# projet_pcb_bluepill_f103_SchDoc.net
KiCad netlist of a schematic drawn in EasyEDA
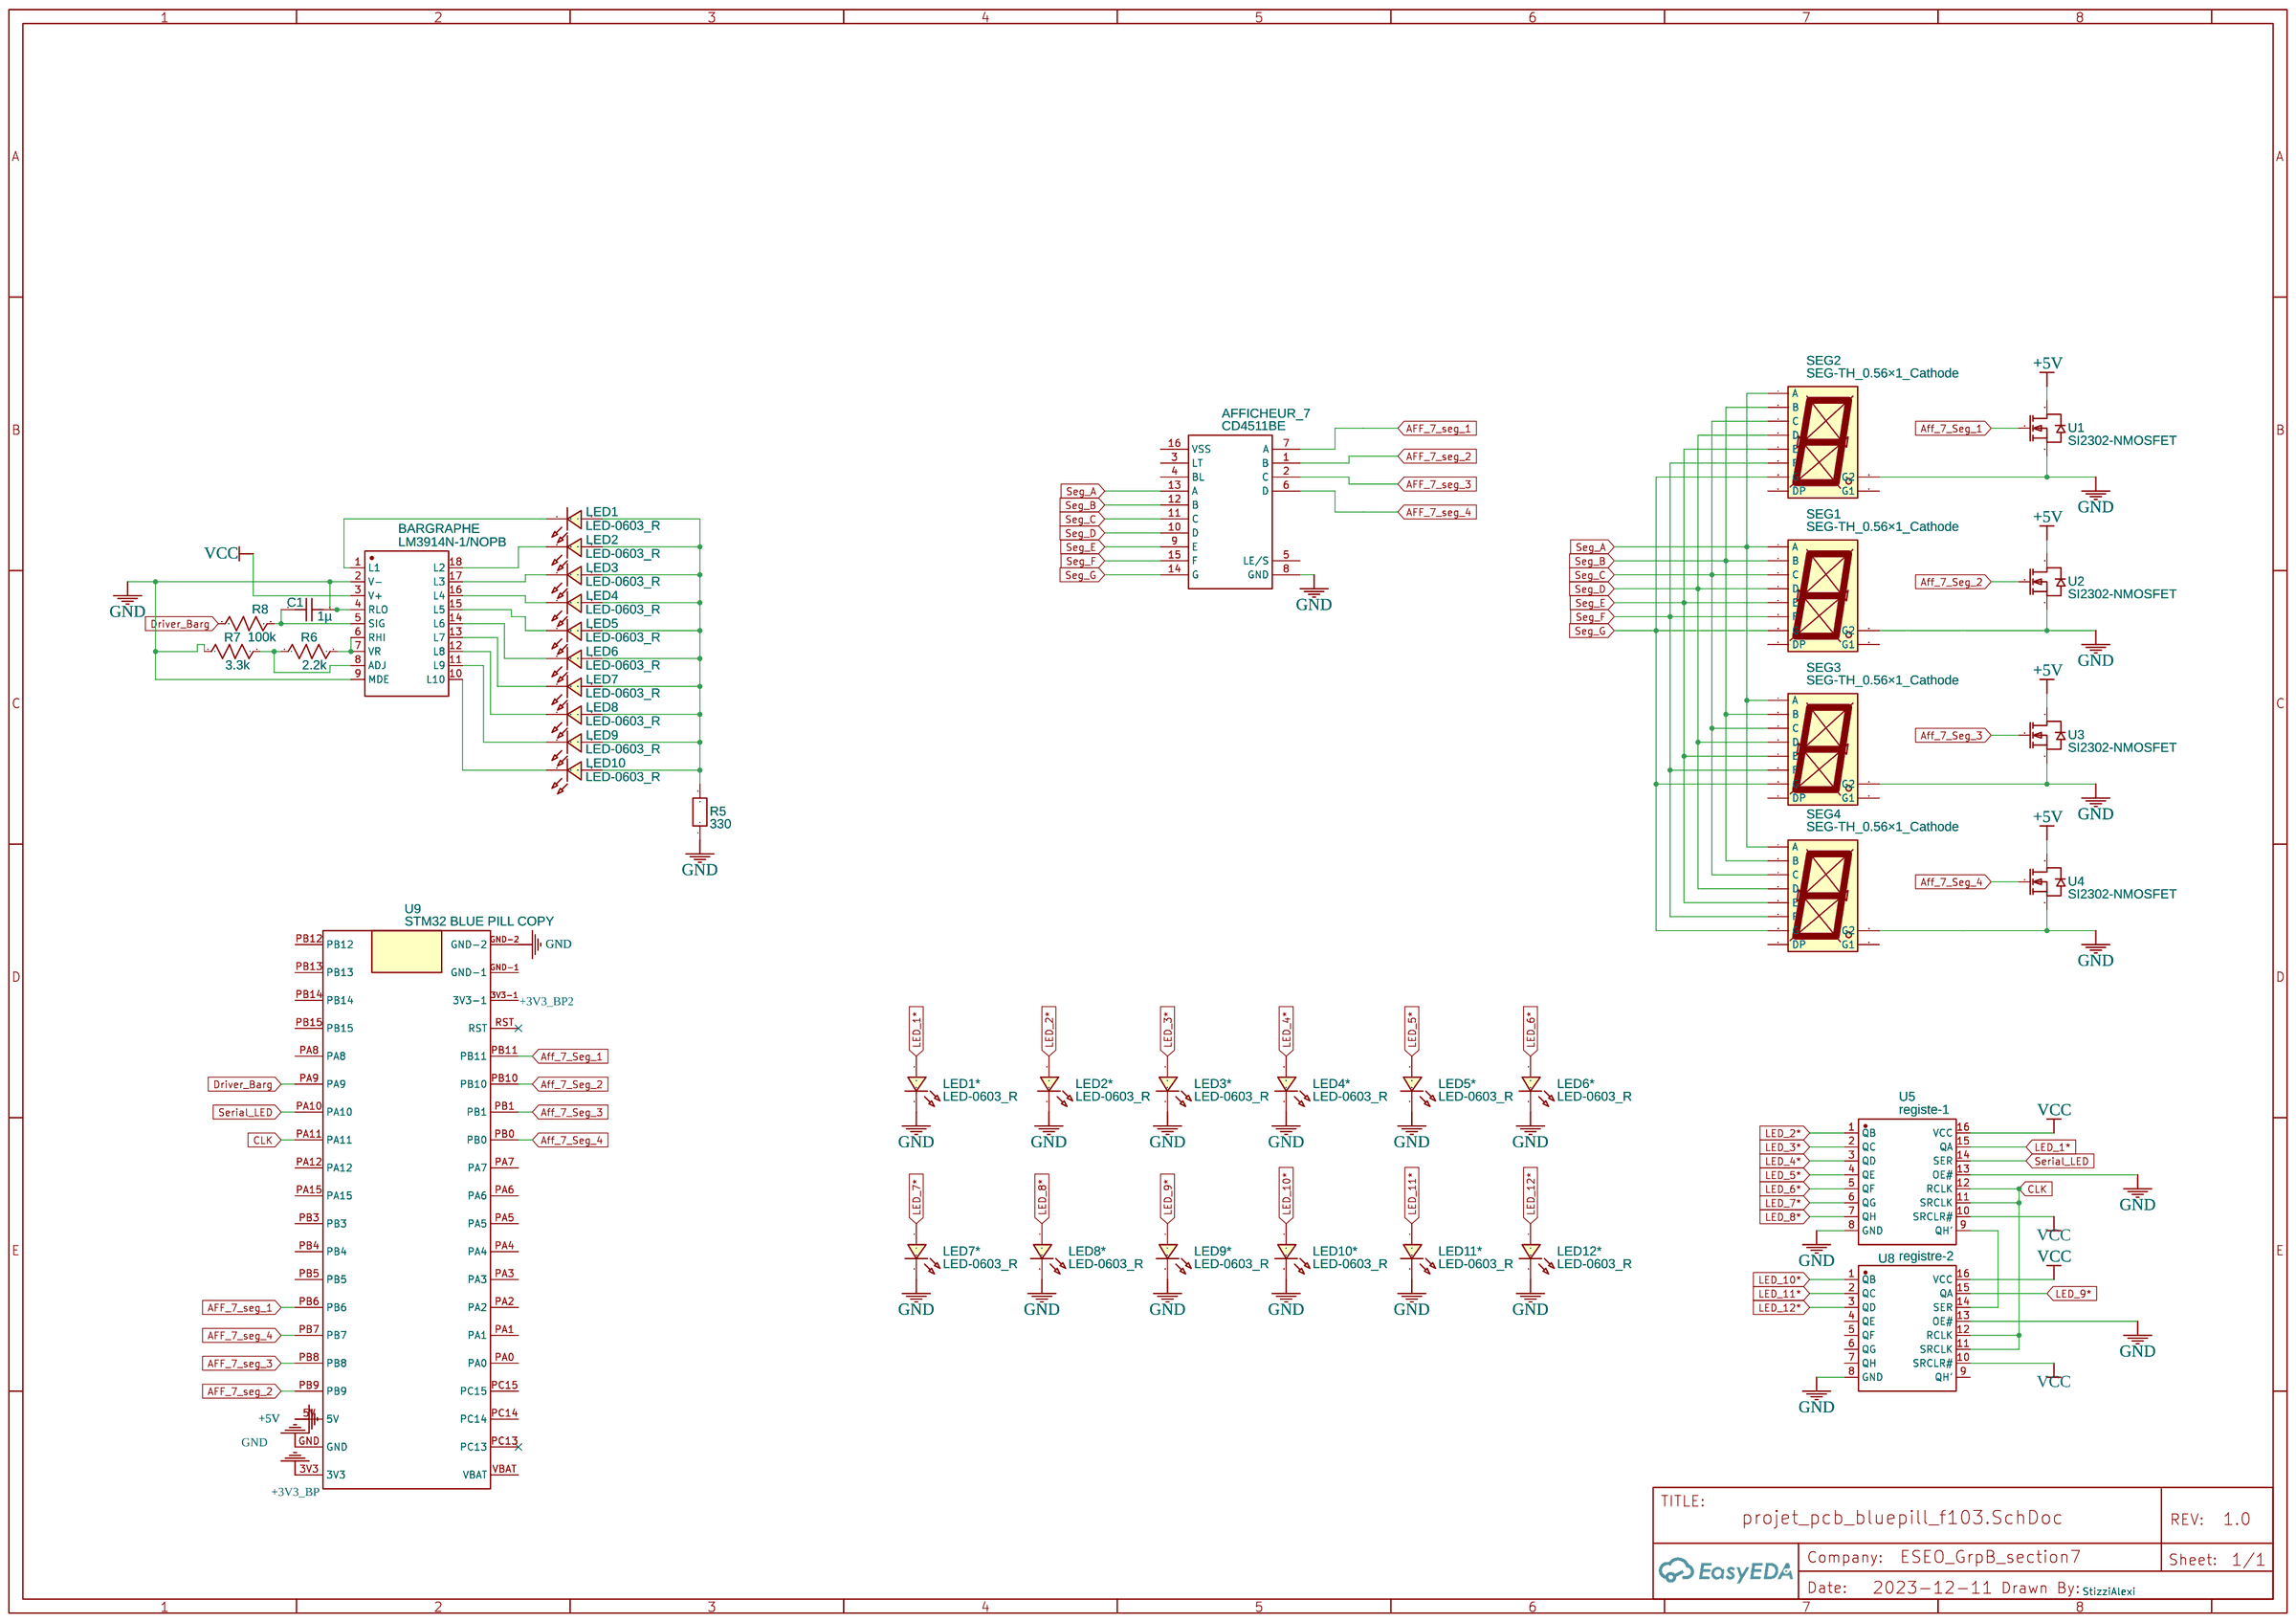
[diagram p0: schematic sheet]

(export (version "E")
  (design (tool "Eeschema 10.0.6"))
  (components
    (comp (ref "AFFICHEUR_7") (value "CD4511BE") (libsource (lib "") (part "CD4511BE")))
    (comp (ref "BARGRAPHE")
      (value "LM3914N-1/NOPB")
      (fields (field (name "Manufacturer") "TI(德州仪器)"))
      (libsource (lib "") (part "LM3914N-1/NOPB"))
    )
    (comp (ref "C1") (value "1µ") (libsource (lib "") (part "C_0603_US")))
    (comp (ref "LED1")
      (value "LED-0603_R")
      (fields
        (field (name "Manufacturer Part") "19-217/R6C-AL1M2VY/3T")
        (field (name "Manufacturer") "EVERLIGHT(台湾亿光)")
      )
      (libsource (lib "") (part "LED-0603_R_1"))
    )
    (comp (ref "LED1*")
      (value "LED-0603_R")
      (fields
        (field (name "Manufacturer Part") "19-217/R6C-AL1M2VY/3T")
        (field (name "Manufacturer") "EVERLIGHT(台湾亿光)")
      )
      (libsource (lib "") (part "LED-0603_R"))
    )
    (comp (ref "LED2")
      (value "LED-0603_R")
      (fields
        (field (name "Manufacturer Part") "19-217/R6C-AL1M2VY/3T")
        (field (name "Manufacturer") "EVERLIGHT(台湾亿光)")
      )
      (libsource (lib "") (part "LED-0603_R_1"))
    )
    (comp (ref "LED2*")
      (value "LED-0603_R")
      (fields
        (field (name "Manufacturer Part") "19-217/R6C-AL1M2VY/3T")
        (field (name "Manufacturer") "EVERLIGHT(台湾亿光)")
      )
      (libsource (lib "") (part "LED-0603_R_8"))
    )
    (comp (ref "LED3")
      (value "LED-0603_R")
      (fields
        (field (name "Manufacturer Part") "19-217/R6C-AL1M2VY/3T")
        (field (name "Manufacturer") "EVERLIGHT(台湾亿光)")
      )
      (libsource (lib "") (part "LED-0603_R_1"))
    )
    (comp (ref "LED3*")
      (value "LED-0603_R")
      (fields
        (field (name "Manufacturer Part") "19-217/R6C-AL1M2VY/3T")
        (field (name "Manufacturer") "EVERLIGHT(台湾亿光)")
      )
      (libsource (lib "") (part "LED-0603_R_2"))
    )
    (comp (ref "LED4")
      (value "LED-0603_R")
      (fields
        (field (name "Manufacturer Part") "19-217/R6C-AL1M2VY/3T")
        (field (name "Manufacturer") "EVERLIGHT(台湾亿光)")
      )
      (libsource (lib "") (part "LED-0603_R_1"))
    )
    (comp (ref "LED4*")
      (value "LED-0603_R")
      (fields
        (field (name "Manufacturer Part") "19-217/R6C-AL1M2VY/3T")
        (field (name "Manufacturer") "EVERLIGHT(台湾亿光)")
      )
      (libsource (lib "") (part "LED-0603_R_6"))
    )
    (comp (ref "LED5")
      (value "LED-0603_R")
      (fields
        (field (name "Manufacturer Part") "19-217/R6C-AL1M2VY/3T")
        (field (name "Manufacturer") "EVERLIGHT(台湾亿光)")
      )
      (libsource (lib "") (part "LED-0603_R_1"))
    )
    (comp (ref "LED5*")
      (value "LED-0603_R")
      (fields
        (field (name "Manufacturer Part") "19-217/R6C-AL1M2VY/3T")
        (field (name "Manufacturer") "EVERLIGHT(台湾亿光)")
      )
      (libsource (lib "") (part "LED-0603_R_7"))
    )
    (comp (ref "LED6")
      (value "LED-0603_R")
      (fields
        (field (name "Manufacturer Part") "19-217/R6C-AL1M2VY/3T")
        (field (name "Manufacturer") "EVERLIGHT(台湾亿光)")
      )
      (libsource (lib "") (part "LED-0603_R_1"))
    )
    (comp (ref "LED6*")
      (value "LED-0603_R")
      (fields
        (field (name "Manufacturer Part") "19-217/R6C-AL1M2VY/3T")
        (field (name "Manufacturer") "EVERLIGHT(台湾亿光)")
      )
      (libsource (lib "") (part "LED-0603_R_12"))
    )
    (comp (ref "LED7")
      (value "LED-0603_R")
      (fields
        (field (name "Manufacturer Part") "19-217/R6C-AL1M2VY/3T")
        (field (name "Manufacturer") "EVERLIGHT(台湾亿光)")
      )
      (libsource (lib "") (part "LED-0603_R_1"))
    )
    (comp (ref "LED7*")
      (value "LED-0603_R")
      (fields
        (field (name "Manufacturer Part") "19-217/R6C-AL1M2VY/3T")
        (field (name "Manufacturer") "EVERLIGHT(台湾亿光)")
      )
      (libsource (lib "") (part "LED-0603_R_4"))
    )
    (comp (ref "LED8")
      (value "LED-0603_R")
      (fields
        (field (name "Manufacturer Part") "19-217/R6C-AL1M2VY/3T")
        (field (name "Manufacturer") "EVERLIGHT(台湾亿光)")
      )
      (libsource (lib "") (part "LED-0603_R_1"))
    )
    (comp (ref "LED8*")
      (value "LED-0603_R")
      (fields
        (field (name "Manufacturer Part") "19-217/R6C-AL1M2VY/3T")
        (field (name "Manufacturer") "EVERLIGHT(台湾亿光)")
      )
      (libsource (lib "") (part "LED-0603_R_5"))
    )
    (comp (ref "LED9")
      (value "LED-0603_R")
      (fields
        (field (name "Manufacturer Part") "19-217/R6C-AL1M2VY/3T")
        (field (name "Manufacturer") "EVERLIGHT(台湾亿光)")
      )
      (libsource (lib "") (part "LED-0603_R_1"))
    )
    (comp (ref "LED9*")
      (value "LED-0603_R")
      (fields
        (field (name "Manufacturer Part") "19-217/R6C-AL1M2VY/3T")
        (field (name "Manufacturer") "EVERLIGHT(台湾亿光)")
      )
      (libsource (lib "") (part "LED-0603_R_9"))
    )
    (comp (ref "LED10")
      (value "LED-0603_R")
      (fields
        (field (name "Manufacturer Part") "19-217/R6C-AL1M2VY/3T")
        (field (name "Manufacturer") "EVERLIGHT(台湾亿光)")
      )
      (libsource (lib "") (part "LED-0603_R_1"))
    )
    (comp (ref "LED10*")
      (value "LED-0603_R")
      (fields
        (field (name "Manufacturer Part") "19-217/R6C-AL1M2VY/3T")
        (field (name "Manufacturer") "EVERLIGHT(台湾亿光)")
      )
      (libsource (lib "") (part "LED-0603_R_10"))
    )
    (comp (ref "LED11*")
      (value "LED-0603_R")
      (fields
        (field (name "Manufacturer Part") "19-217/R6C-AL1M2VY/3T")
        (field (name "Manufacturer") "EVERLIGHT(台湾亿光)")
      )
      (libsource (lib "") (part "LED-0603_R_11"))
    )
    (comp (ref "LED12*")
      (value "LED-0603_R")
      (fields
        (field (name "Manufacturer Part") "19-217/R6C-AL1M2VY/3T")
        (field (name "Manufacturer") "EVERLIGHT(台湾亿光)")
      )
      (libsource (lib "") (part "LED-0603_R_3"))
    )
    (comp (ref "R5") (value "330") (libsource (lib "") (part "R_0603_EU")))
    (comp (ref "R6") (value "2.2k") (libsource (lib "") (part "R_0603_US")))
    (comp (ref "R7") (value "3.3k") (libsource (lib "") (part "R_0603_US")))
    (comp (ref "R8") (value "100k") (libsource (lib "") (part "R_0603_US")))
    (comp (ref "SEG1")
      (value "SEG-TH_0.56×1_Cathode")
      (fields (field (name "Manufacturer") "志浩"))
      (libsource (lib "") (part "SEG-TH_0.56×1_Cathode"))
    )
    (comp (ref "SEG2")
      (value "SEG-TH_0.56×1_Cathode")
      (fields (field (name "Manufacturer") "志浩"))
      (libsource (lib "") (part "SEG-TH_0.56×1_Cathode"))
    )
    (comp (ref "SEG3")
      (value "SEG-TH_0.56×1_Cathode")
      (fields (field (name "Manufacturer") "志浩"))
      (libsource (lib "") (part "SEG-TH_0.56×1_Cathode"))
    )
    (comp (ref "SEG4")
      (value "SEG-TH_0.56×1_Cathode")
      (fields (field (name "Manufacturer") "志浩"))
      (libsource (lib "") (part "SEG-TH_0.56×1_Cathode"))
    )
    (comp (ref "U1")
      (value "SI2302-NMOSFET")
      (fields (field (name "Manufacturer Part") "si2302-nmosfet"))
      (libsource (lib "") (part "SI2302-NMOSFET"))
    )
    (comp (ref "U2")
      (value "SI2302-NMOSFET")
      (fields (field (name "Manufacturer Part") "si2302-nmosfet"))
      (libsource (lib "") (part "SI2302-NMOSFET"))
    )
    (comp (ref "U3")
      (value "SI2302-NMOSFET")
      (fields (field (name "Manufacturer Part") "si2302-nmosfet"))
      (libsource (lib "") (part "SI2302-NMOSFET"))
    )
    (comp (ref "U4")
      (value "SI2302-NMOSFET")
      (fields (field (name "Manufacturer Part") "si2302-nmosfet"))
      (libsource (lib "") (part "SI2302-NMOSFET"))
    )
    (comp (ref "U5")
      (value "registe-1")
      (fields (field (name "Manufacturer Part") "CD74HC595E") (field (name "Manufacturer") "TI(德州仪器)"))
      (libsource (lib "") (part "CD74HC595E"))
    )
    (comp (ref "U8")
      (value "registre-2")
      (fields (field (name "Manufacturer Part") "CD74HC595E") (field (name "Manufacturer") "TI(德州仪器)"))
      (libsource (lib "") (part "CD74HC595E"))
    )
    (comp (ref "U9") (value "STM32 BLUE PILL COPY") (libsource (lib "") (part "STM32 BLUE PILL COPY")))
  )
  (nets
    (net (code "1") (name "+3V3_BP") (class "Default")
      (node (ref "U9") (pin "3V3") (pinfunction "3V3_3V3") (pintype "passive"))
    )
    (net (code "2") (name "+5V") (class "Default")
      (node (ref "U1") (pin "3") (pinfunction "D_3") (pintype "unspecified"))
      (node (ref "U2") (pin "3") (pinfunction "D_3") (pintype "unspecified"))
      (node (ref "U3") (pin "3") (pinfunction "D_3") (pintype "unspecified"))
      (node (ref "U4") (pin "3") (pinfunction "D_3") (pintype "unspecified"))
      (node (ref "U9") (pin "5V") (pinfunction "5V_5V") (pintype "passive"))
    )
    (net (code "4") (name "AFF_7_seg_1") (class "Default")
      (node (ref "AFFICHEUR_7") (pin "7") (pinfunction "A_7") (pintype "unspecified"))
      (node (ref "U9") (pin "PB6") (pinfunction "PB6_PB6") (pintype "bidirectional"))
    )
    (net (code "5") (name "AFF_7_seg_2") (class "Default")
      (node (ref "AFFICHEUR_7") (pin "1") (pinfunction "B_1") (pintype "unspecified"))
      (node (ref "U9") (pin "PB9") (pinfunction "PB9_PB9") (pintype "bidirectional"))
    )
    (net (code "6") (name "AFF_7_seg_3") (class "Default")
      (node (ref "AFFICHEUR_7") (pin "2") (pinfunction "C_2") (pintype "unspecified"))
      (node (ref "U9") (pin "PB8") (pinfunction "PB8_PB8") (pintype "bidirectional"))
    )
    (net (code "7") (name "AFF_7_seg_4") (class "Default")
      (node (ref "AFFICHEUR_7") (pin "6") (pinfunction "D_6") (pintype "unspecified"))
      (node (ref "U9") (pin "PB7") (pinfunction "PB7_PB7") (pintype "bidirectional"))
    )
    (net (code "8") (name "Aff_7_Seg_1") (class "Default")
      (node (ref "U1") (pin "1") (pinfunction "G_1") (pintype "unspecified"))
      (node (ref "U9") (pin "PB11") (pinfunction "PB11_PB11") (pintype "bidirectional"))
    )
    (net (code "9") (name "Aff_7_Seg_2") (class "Default")
      (node (ref "U2") (pin "1") (pinfunction "G_1") (pintype "unspecified"))
      (node (ref "U9") (pin "PB10") (pinfunction "PB10_PB10") (pintype "bidirectional"))
    )
    (net (code "10") (name "Aff_7_Seg_3") (class "Default")
      (node (ref "U3") (pin "1") (pinfunction "G_1") (pintype "unspecified"))
      (node (ref "U9") (pin "PB1") (pinfunction "PB1_PB1") (pintype "bidirectional"))
    )
    (net (code "11") (name "Aff_7_Seg_4") (class "Default")
      (node (ref "U4") (pin "1") (pinfunction "G_1") (pintype "unspecified"))
      (node (ref "U9") (pin "PB0") (pinfunction "PB0_PB0") (pintype "bidirectional"))
    )
    (net (code "12") (name "CLK") (class "Default")
      (node (ref "U5") (pin "11") (pinfunction "SRCLK_11") (pintype "unspecified"))
      (node (ref "U5") (pin "12") (pinfunction "RCLK_12") (pintype "unspecified"))
      (node (ref "U8") (pin "11") (pinfunction "SRCLK_11") (pintype "unspecified"))
      (node (ref "U8") (pin "12") (pinfunction "RCLK_12") (pintype "unspecified"))
      (node (ref "U9") (pin "PA11") (pinfunction "PA11_PA11") (pintype "bidirectional"))
    )
    (net (code "13") (name "Driver_Barg") (class "Default")
      (node (ref "R8") (pin "1") (pinfunction "1_1") (pintype "unspecified"))
      (node (ref "U9") (pin "PA9") (pinfunction "PA9_PA9") (pintype "bidirectional"))
    )
    (net (code "14") (name "GND") (class "Default")
      (node (ref "AFFICHEUR_7") (pin "8") (pinfunction "GND_8") (pintype "unspecified"))
      (node (ref "BARGRAPHE") (pin "2") (pinfunction "V-_2") (pintype "unspecified"))
      (node (ref "BARGRAPHE") (pin "4") (pinfunction "RLO_4") (pintype "unspecified"))
      (node (ref "BARGRAPHE") (pin "9") (pinfunction "MDE_9") (pintype "unspecified"))
      (node (ref "C1") (pin "2") (pinfunction "2_2") (pintype "unspecified"))
      (node (ref "LED1*") (pin "2") (pinfunction "2_2") (pintype "unspecified"))
      (node (ref "LED10*") (pin "2") (pinfunction "2_2") (pintype "unspecified"))
      (node (ref "LED11*") (pin "2") (pinfunction "2_2") (pintype "unspecified"))
      (node (ref "LED12*") (pin "2") (pinfunction "2_2") (pintype "unspecified"))
      (node (ref "LED2*") (pin "2") (pinfunction "2_2") (pintype "unspecified"))
      (node (ref "LED3*") (pin "2") (pinfunction "2_2") (pintype "unspecified"))
      (node (ref "LED4*") (pin "2") (pinfunction "2_2") (pintype "unspecified"))
      (node (ref "LED5*") (pin "2") (pinfunction "2_2") (pintype "unspecified"))
      (node (ref "LED6*") (pin "2") (pinfunction "2_2") (pintype "unspecified"))
      (node (ref "LED7*") (pin "2") (pinfunction "2_2") (pintype "unspecified"))
      (node (ref "LED8*") (pin "2") (pinfunction "2_2") (pintype "unspecified"))
      (node (ref "LED9*") (pin "2") (pinfunction "2_2") (pintype "unspecified"))
      (node (ref "R5") (pin "1") (pinfunction "1_1") (pintype "unspecified"))
      (node (ref "R7") (pin "1") (pinfunction "1_1") (pintype "unspecified"))
      (node (ref "SEG1") (pin "8") (pinfunction "G2_8") (pintype "unspecified"))
      (node (ref "SEG2") (pin "8") (pinfunction "G2_8") (pintype "unspecified"))
      (node (ref "SEG3") (pin "8") (pinfunction "G2_8") (pintype "unspecified"))
      (node (ref "SEG4") (pin "8") (pinfunction "G2_8") (pintype "unspecified"))
      (node (ref "U1") (pin "2") (pinfunction "S_2") (pintype "unspecified"))
      (node (ref "U2") (pin "2") (pinfunction "S_2") (pintype "unspecified"))
      (node (ref "U3") (pin "2") (pinfunction "S_2") (pintype "unspecified"))
      (node (ref "U4") (pin "2") (pinfunction "S_2") (pintype "unspecified"))
      (node (ref "U5") (pin "13") (pinfunction "OE#_13") (pintype "unspecified"))
      (node (ref "U5") (pin "8") (pinfunction "GND_8") (pintype "unspecified"))
      (node (ref "U8") (pin "13") (pinfunction "OE#_13") (pintype "unspecified"))
      (node (ref "U8") (pin "8") (pinfunction "GND_8") (pintype "unspecified"))
      (node (ref "U9") (pin "GND") (pinfunction "GND_GND") (pintype "passive"))
      (node (ref "U9") (pin "GND-2") (pinfunction "GND-2_GND-2") (pintype "passive"))
    )
    (net (code "15") (name "LED_1*") (class "Default")
      (node (ref "LED1*") (pin "1") (pinfunction "1_1") (pintype "unspecified"))
      (node (ref "U5") (pin "15") (pinfunction "QA_15") (pintype "unspecified"))
    )
    (net (code "16") (name "LED_2*") (class "Default")
      (node (ref "LED2*") (pin "1") (pinfunction "1_1") (pintype "unspecified"))
      (node (ref "U5") (pin "1") (pinfunction "QB_1") (pintype "unspecified"))
    )
    (net (code "17") (name "LED_3*") (class "Default")
      (node (ref "LED3*") (pin "1") (pinfunction "1_1") (pintype "unspecified"))
      (node (ref "U5") (pin "2") (pinfunction "QC_2") (pintype "unspecified"))
    )
    (net (code "18") (name "LED_4*") (class "Default")
      (node (ref "LED4*") (pin "1") (pinfunction "1_1") (pintype "unspecified"))
      (node (ref "U5") (pin "3") (pinfunction "QD_3") (pintype "unspecified"))
    )
    (net (code "19") (name "LED_5*") (class "Default")
      (node (ref "LED5*") (pin "1") (pinfunction "1_1") (pintype "unspecified"))
      (node (ref "U5") (pin "4") (pinfunction "QE_4") (pintype "unspecified"))
    )
    (net (code "20") (name "LED_6*") (class "Default")
      (node (ref "LED6*") (pin "1") (pinfunction "1_1") (pintype "unspecified"))
      (node (ref "U5") (pin "5") (pinfunction "QF_5") (pintype "unspecified"))
    )
    (net (code "21") (name "LED_7*") (class "Default")
      (node (ref "LED7*") (pin "1") (pinfunction "1_1") (pintype "unspecified"))
      (node (ref "U5") (pin "6") (pinfunction "QG_6") (pintype "unspecified"))
    )
    (net (code "22") (name "LED_8*") (class "Default")
      (node (ref "LED8*") (pin "1") (pinfunction "1_1") (pintype "unspecified"))
      (node (ref "U5") (pin "7") (pinfunction "QH_7") (pintype "unspecified"))
    )
    (net (code "23") (name "LED_9*") (class "Default")
      (node (ref "LED9*") (pin "1") (pinfunction "1_1") (pintype "unspecified"))
      (node (ref "U8") (pin "15") (pinfunction "QA_15") (pintype "unspecified"))
    )
    (net (code "24") (name "LED_10*") (class "Default")
      (node (ref "LED10*") (pin "1") (pinfunction "1_1") (pintype "unspecified"))
      (node (ref "U8") (pin "1") (pinfunction "QB_1") (pintype "unspecified"))
    )
    (net (code "25") (name "LED_11*") (class "Default")
      (node (ref "LED11*") (pin "1") (pinfunction "1_1") (pintype "unspecified"))
      (node (ref "U8") (pin "2") (pinfunction "QC_2") (pintype "unspecified"))
    )
    (net (code "26") (name "LED_12*") (class "Default")
      (node (ref "LED12*") (pin "1") (pinfunction "1_1") (pintype "unspecified"))
      (node (ref "U8") (pin "3") (pinfunction "QD_3") (pintype "unspecified"))
    )
    (net (code "27") (name "Net-(BARGRAPHE-ADJ)") (class "Default")
      (node (ref "BARGRAPHE") (pin "8") (pinfunction "ADJ_8") (pintype "unspecified"))
      (node (ref "R6") (pin "1") (pinfunction "1_1") (pintype "unspecified"))
      (node (ref "R7") (pin "2") (pinfunction "2_2") (pintype "unspecified"))
    )
    (net (code "28") (name "Net-(BARGRAPHE-L1)") (class "Default")
      (node (ref "BARGRAPHE") (pin "1") (pinfunction "L1_1") (pintype "unspecified"))
      (node (ref "LED1") (pin "2") (pinfunction "2_2") (pintype "unspecified"))
    )
    (net (code "29") (name "Net-(BARGRAPHE-L2)") (class "Default")
      (node (ref "BARGRAPHE") (pin "18") (pinfunction "L2_18") (pintype "unspecified"))
      (node (ref "LED2") (pin "2") (pinfunction "2_2") (pintype "unspecified"))
    )
    (net (code "30") (name "Net-(BARGRAPHE-L3)") (class "Default")
      (node (ref "BARGRAPHE") (pin "17") (pinfunction "L3_17") (pintype "unspecified"))
      (node (ref "LED3") (pin "2") (pinfunction "2_2") (pintype "unspecified"))
    )
    (net (code "31") (name "Net-(BARGRAPHE-L4)") (class "Default")
      (node (ref "BARGRAPHE") (pin "16") (pinfunction "L4_16") (pintype "unspecified"))
      (node (ref "LED4") (pin "2") (pinfunction "2_2") (pintype "unspecified"))
    )
    (net (code "32") (name "Net-(BARGRAPHE-L5)") (class "Default")
      (node (ref "BARGRAPHE") (pin "15") (pinfunction "L5_15") (pintype "unspecified"))
      (node (ref "LED5") (pin "2") (pinfunction "2_2") (pintype "unspecified"))
    )
    (net (code "33") (name "Net-(BARGRAPHE-L6)") (class "Default")
      (node (ref "BARGRAPHE") (pin "14") (pinfunction "L6_14") (pintype "unspecified"))
      (node (ref "LED6") (pin "2") (pinfunction "2_2") (pintype "unspecified"))
    )
    (net (code "34") (name "Net-(BARGRAPHE-L7)") (class "Default")
      (node (ref "BARGRAPHE") (pin "13") (pinfunction "L7_13") (pintype "unspecified"))
      (node (ref "LED7") (pin "2") (pinfunction "2_2") (pintype "unspecified"))
    )
    (net (code "35") (name "Net-(BARGRAPHE-L8)") (class "Default")
      (node (ref "BARGRAPHE") (pin "12") (pinfunction "L8_12") (pintype "unspecified"))
      (node (ref "LED8") (pin "2") (pinfunction "2_2") (pintype "unspecified"))
    )
    (net (code "36") (name "Net-(BARGRAPHE-L9)") (class "Default")
      (node (ref "BARGRAPHE") (pin "11") (pinfunction "L9_11") (pintype "unspecified"))
      (node (ref "LED9") (pin "2") (pinfunction "2_2") (pintype "unspecified"))
    )
    (net (code "37") (name "Net-(BARGRAPHE-L10)") (class "Default")
      (node (ref "BARGRAPHE") (pin "10") (pinfunction "L10_10") (pintype "unspecified"))
      (node (ref "LED10") (pin "2") (pinfunction "2_2") (pintype "unspecified"))
    )
    (net (code "38") (name "Net-(BARGRAPHE-RHI)") (class "Default")
      (node (ref "BARGRAPHE") (pin "6") (pinfunction "RHI_6") (pintype "unspecified"))
      (node (ref "BARGRAPHE") (pin "7") (pinfunction "VR_7") (pintype "unspecified"))
      (node (ref "R6") (pin "2") (pinfunction "2_2") (pintype "unspecified"))
    )
    (net (code "39") (name "Net-(BARGRAPHE-SIG)") (class "Default")
      (node (ref "BARGRAPHE") (pin "5") (pinfunction "SIG_5") (pintype "unspecified"))
      (node (ref "C1") (pin "1") (pinfunction "1_1") (pintype "unspecified"))
      (node (ref "R8") (pin "2") (pinfunction "2_2") (pintype "unspecified"))
    )
    (net (code "40") (name "Net-(LED1-Pad1)") (class "Default")
      (node (ref "LED1") (pin "1") (pinfunction "1_1") (pintype "unspecified"))
      (node (ref "LED10") (pin "1") (pinfunction "1_1") (pintype "unspecified"))
      (node (ref "LED2") (pin "1") (pinfunction "1_1") (pintype "unspecified"))
      (node (ref "LED3") (pin "1") (pinfunction "1_1") (pintype "unspecified"))
      (node (ref "LED4") (pin "1") (pinfunction "1_1") (pintype "unspecified"))
      (node (ref "LED5") (pin "1") (pinfunction "1_1") (pintype "unspecified"))
      (node (ref "LED6") (pin "1") (pinfunction "1_1") (pintype "unspecified"))
      (node (ref "LED7") (pin "1") (pinfunction "1_1") (pintype "unspecified"))
      (node (ref "LED8") (pin "1") (pinfunction "1_1") (pintype "unspecified"))
      (node (ref "LED9") (pin "1") (pinfunction "1_1") (pintype "unspecified"))
      (node (ref "R5") (pin "2") (pinfunction "2_2") (pintype "unspecified"))
    )
    (net (code "41") (name "Net-(U5-QH’)") (class "Default")
      (node (ref "U5") (pin "9") (pinfunction "QH’_9") (pintype "unspecified"))
      (node (ref "U8") (pin "14") (pinfunction "SER_14") (pintype "unspecified"))
    )
    (net (code "42") (name "Seg_A") (class "Default")
      (node (ref "AFFICHEUR_7") (pin "13") (pinfunction "A_13") (pintype "unspecified"))
      (node (ref "SEG1") (pin "7") (pinfunction "A_7") (pintype "unspecified"))
      (node (ref "SEG2") (pin "7") (pinfunction "A_7") (pintype "unspecified"))
      (node (ref "SEG3") (pin "7") (pinfunction "A_7") (pintype "unspecified"))
      (node (ref "SEG4") (pin "7") (pinfunction "A_7") (pintype "unspecified"))
    )
    (net (code "43") (name "Seg_B") (class "Default")
      (node (ref "AFFICHEUR_7") (pin "12") (pinfunction "B_12") (pintype "unspecified"))
      (node (ref "SEG1") (pin "6") (pinfunction "B_6") (pintype "unspecified"))
      (node (ref "SEG2") (pin "6") (pinfunction "B_6") (pintype "unspecified"))
      (node (ref "SEG3") (pin "6") (pinfunction "B_6") (pintype "unspecified"))
      (node (ref "SEG4") (pin "6") (pinfunction "B_6") (pintype "unspecified"))
    )
    (net (code "44") (name "Seg_C") (class "Default")
      (node (ref "AFFICHEUR_7") (pin "11") (pinfunction "C_11") (pintype "unspecified"))
      (node (ref "SEG1") (pin "4") (pinfunction "C_4") (pintype "unspecified"))
      (node (ref "SEG2") (pin "4") (pinfunction "C_4") (pintype "unspecified"))
      (node (ref "SEG3") (pin "4") (pinfunction "C_4") (pintype "unspecified"))
      (node (ref "SEG4") (pin "4") (pinfunction "C_4") (pintype "unspecified"))
    )
    (net (code "45") (name "Seg_D") (class "Default")
      (node (ref "AFFICHEUR_7") (pin "10") (pinfunction "D_10") (pintype "unspecified"))
      (node (ref "SEG1") (pin "2") (pinfunction "D_2") (pintype "unspecified"))
      (node (ref "SEG2") (pin "2") (pinfunction "D_2") (pintype "unspecified"))
      (node (ref "SEG3") (pin "2") (pinfunction "D_2") (pintype "unspecified"))
      (node (ref "SEG4") (pin "2") (pinfunction "D_2") (pintype "unspecified"))
    )
    (net (code "46") (name "Seg_E") (class "Default")
      (node (ref "AFFICHEUR_7") (pin "9") (pinfunction "E_9") (pintype "unspecified"))
      (node (ref "SEG1") (pin "1") (pinfunction "E_1") (pintype "unspecified"))
      (node (ref "SEG2") (pin "1") (pinfunction "E_1") (pintype "unspecified"))
      (node (ref "SEG3") (pin "1") (pinfunction "E_1") (pintype "unspecified"))
      (node (ref "SEG4") (pin "1") (pinfunction "E_1") (pintype "unspecified"))
    )
    (net (code "47") (name "Seg_F") (class "Default")
      (node (ref "AFFICHEUR_7") (pin "15") (pinfunction "F_15") (pintype "unspecified"))
      (node (ref "SEG1") (pin "9") (pinfunction "F_9") (pintype "unspecified"))
      (node (ref "SEG2") (pin "9") (pinfunction "F_9") (pintype "unspecified"))
      (node (ref "SEG3") (pin "9") (pinfunction "F_9") (pintype "unspecified"))
      (node (ref "SEG4") (pin "9") (pinfunction "F_9") (pintype "unspecified"))
    )
    (net (code "48") (name "Seg_G") (class "Default")
      (node (ref "AFFICHEUR_7") (pin "14") (pinfunction "G_14") (pintype "unspecified"))
      (node (ref "SEG1") (pin "10") (pinfunction "G_10") (pintype "unspecified"))
      (node (ref "SEG2") (pin "10") (pinfunction "G_10") (pintype "unspecified"))
      (node (ref "SEG3") (pin "10") (pinfunction "G_10") (pintype "unspecified"))
      (node (ref "SEG4") (pin "10") (pinfunction "G_10") (pintype "unspecified"))
    )
    (net (code "49") (name "Serial_LED") (class "Default")
      (node (ref "U5") (pin "14") (pinfunction "SER_14") (pintype "unspecified"))
      (node (ref "U9") (pin "PA10") (pinfunction "PA10_PA10") (pintype "bidirectional"))
    )
    (net (code "50") (name "VCC") (class "Default")
      (node (ref "BARGRAPHE") (pin "3") (pinfunction "V+_3") (pintype "unspecified"))
      (node (ref "U5") (pin "10") (pinfunction "SRCLR#_10") (pintype "unspecified"))
      (node (ref "U5") (pin "16") (pinfunction "VCC_16") (pintype "unspecified"))
      (node (ref "U8") (pin "10") (pinfunction "SRCLR#_10") (pintype "unspecified"))
      (node (ref "U8") (pin "16") (pinfunction "VCC_16") (pintype "unspecified"))
    )
    (net (code "51") (name "unconnected-(AFFICHEUR_7-BL-Pad4)") (class "Default")
      (node (ref "AFFICHEUR_7") (pin "4") (pinfunction "BL_4") (pintype "unspecified"))
    )
    (net (code "52") (name "unconnected-(AFFICHEUR_7-LE{slash}S-Pad5)") (class "Default")
      (node (ref "AFFICHEUR_7") (pin "5") (pinfunction "LE/S_5") (pintype "unspecified"))
    )
    (net (code "53") (name "unconnected-(AFFICHEUR_7-LT-Pad3)") (class "Default")
      (node (ref "AFFICHEUR_7") (pin "3") (pinfunction "LT_3") (pintype "unspecified"))
    )
    (net (code "54") (name "unconnected-(AFFICHEUR_7-VSS-Pad16)") (class "Default")
      (node (ref "AFFICHEUR_7") (pin "16") (pinfunction "VSS_16") (pintype "unspecified"))
    )
    (net (code "55") (name "unconnected-(SEG1-DP-Pad5)") (class "Default")
      (node (ref "SEG1") (pin "5") (pinfunction "DP_5") (pintype "unspecified"))
    )
    (net (code "56") (name "unconnected-(SEG1-G1-Pad3)") (class "Default")
      (node (ref "SEG1") (pin "3") (pinfunction "G1_3") (pintype "unspecified"))
    )
    (net (code "57") (name "unconnected-(SEG2-DP-Pad5)") (class "Default")
      (node (ref "SEG2") (pin "5") (pinfunction "DP_5") (pintype "unspecified"))
    )
    (net (code "58") (name "unconnected-(SEG2-G1-Pad3)") (class "Default")
      (node (ref "SEG2") (pin "3") (pinfunction "G1_3") (pintype "unspecified"))
    )
    (net (code "59") (name "unconnected-(SEG3-DP-Pad5)") (class "Default")
      (node (ref "SEG3") (pin "5") (pinfunction "DP_5") (pintype "unspecified"))
    )
    (net (code "60") (name "unconnected-(SEG3-G1-Pad3)") (class "Default")
      (node (ref "SEG3") (pin "3") (pinfunction "G1_3") (pintype "unspecified"))
    )
    (net (code "61") (name "unconnected-(SEG4-DP-Pad5)") (class "Default")
      (node (ref "SEG4") (pin "5") (pinfunction "DP_5") (pintype "unspecified"))
    )
    (net (code "62") (name "unconnected-(SEG4-G1-Pad3)") (class "Default")
      (node (ref "SEG4") (pin "3") (pinfunction "G1_3") (pintype "unspecified"))
    )
    (net (code "63") (name "unconnected-(U8-QE-Pad4)") (class "Default")
      (node (ref "U8") (pin "4") (pinfunction "QE_4") (pintype "unspecified"))
    )
    (net (code "64") (name "unconnected-(U8-QF-Pad5)") (class "Default")
      (node (ref "U8") (pin "5") (pinfunction "QF_5") (pintype "unspecified"))
    )
    (net (code "65") (name "unconnected-(U8-QG-Pad6)") (class "Default")
      (node (ref "U8") (pin "6") (pinfunction "QG_6") (pintype "unspecified"))
    )
    (net (code "66") (name "unconnected-(U8-QH-Pad7)") (class "Default")
      (node (ref "U8") (pin "7") (pinfunction "QH_7") (pintype "unspecified"))
    )
    (net (code "67") (name "unconnected-(U8-QH’-Pad9)") (class "Default")
      (node (ref "U8") (pin "9") (pinfunction "QH’_9") (pintype "unspecified"))
    )
    (net (code "68") (name "unconnected-(U9-Pad3V3-1)") (class "Default")
      (node (ref "U9") (pin "3V3-1") (pinfunction "3V3-1_3V3-1") (pintype "passive"))
    )
    (net (code "69") (name "unconnected-(U9-PadGND-1)") (class "Default")
      (node (ref "U9") (pin "GND-1") (pinfunction "GND-1_GND-1") (pintype "passive"))
    )
    (net (code "70") (name "unconnected-(U9-PadPA0)") (class "Default")
      (node (ref "U9") (pin "PA0") (pinfunction "PA0_PA0") (pintype "bidirectional"))
    )
    (net (code "71") (name "unconnected-(U9-PadPA1)") (class "Default")
      (node (ref "U9") (pin "PA1") (pinfunction "PA1_PA1") (pintype "bidirectional"))
    )
    (net (code "72") (name "unconnected-(U9-PadPA2)") (class "Default")
      (node (ref "U9") (pin "PA2") (pinfunction "PA2_PA2") (pintype "bidirectional"))
    )
    (net (code "73") (name "unconnected-(U9-PadPA3)") (class "Default")
      (node (ref "U9") (pin "PA3") (pinfunction "PA3_PA3") (pintype "bidirectional"))
    )
    (net (code "74") (name "unconnected-(U9-PadPA4)") (class "Default")
      (node (ref "U9") (pin "PA4") (pinfunction "PA4_PA4") (pintype "bidirectional"))
    )
    (net (code "75") (name "unconnected-(U9-PadPA5)") (class "Default")
      (node (ref "U9") (pin "PA5") (pinfunction "PA5_PA5") (pintype "bidirectional"))
    )
    (net (code "76") (name "unconnected-(U9-PadPA6)") (class "Default")
      (node (ref "U9") (pin "PA6") (pinfunction "PA6_PA6") (pintype "bidirectional"))
    )
    (net (code "77") (name "unconnected-(U9-PadPA7)") (class "Default")
      (node (ref "U9") (pin "PA7") (pinfunction "PA7_PA7") (pintype "bidirectional"))
    )
    (net (code "78") (name "unconnected-(U9-PadPA8)") (class "Default")
      (node (ref "U9") (pin "PA8") (pinfunction "PA8_PA8") (pintype "bidirectional"))
    )
    (net (code "79") (name "unconnected-(U9-PadPA12)") (class "Default")
      (node (ref "U9") (pin "PA12") (pinfunction "PA12_PA12") (pintype "bidirectional"))
    )
    (net (code "80") (name "unconnected-(U9-PadPA15)") (class "Default")
      (node (ref "U9") (pin "PA15") (pinfunction "PA15_PA15") (pintype "bidirectional"))
    )
    (net (code "81") (name "unconnected-(U9-PadPB3)") (class "Default")
      (node (ref "U9") (pin "PB3") (pinfunction "PB3_PB3") (pintype "unspecified"))
    )
    (net (code "82") (name "unconnected-(U9-PadPB4)") (class "Default")
      (node (ref "U9") (pin "PB4") (pinfunction "PB4_PB4") (pintype "bidirectional"))
    )
    (net (code "83") (name "unconnected-(U9-PadPB5)") (class "Default")
      (node (ref "U9") (pin "PB5") (pinfunction "PB5_PB5") (pintype "bidirectional"))
    )
    (net (code "84") (name "unconnected-(U9-PadPB12)") (class "Default")
      (node (ref "U9") (pin "PB12") (pinfunction "PB12_PB12") (pintype "bidirectional"))
    )
    (net (code "85") (name "unconnected-(U9-PadPB13)") (class "Default")
      (node (ref "U9") (pin "PB13") (pinfunction "PB13_PB13") (pintype "bidirectional"))
    )
    (net (code "86") (name "unconnected-(U9-PadPB14)") (class "Default")
      (node (ref "U9") (pin "PB14") (pinfunction "PB14_PB14") (pintype "bidirectional"))
    )
    (net (code "87") (name "unconnected-(U9-PadPB15)") (class "Default")
      (node (ref "U9") (pin "PB15") (pinfunction "PB15_PB15") (pintype "bidirectional"))
    )
    (net (code "88") (name "unconnected-(U9-PadPC13)") (class "Default")
      (node (ref "U9") (pin "PC13") (pinfunction "PC13_PC13") (pintype "bidirectional+no_connect"))
    )
    (net (code "89") (name "unconnected-(U9-PadPC14)") (class "Default")
      (node (ref "U9") (pin "PC14") (pinfunction "PC14_PC14") (pintype "bidirectional"))
    )
    (net (code "90") (name "unconnected-(U9-PadPC15)") (class "Default")
      (node (ref "U9") (pin "PC15") (pinfunction "PC15_PC15") (pintype "bidirectional"))
    )
    (net (code "91") (name "unconnected-(U9-PadRST)") (class "Default")
      (node (ref "U9") (pin "RST") (pinfunction "RST_RST") (pintype "input+no_connect"))
    )
    (net (code "92") (name "unconnected-(U9-PadVBAT)") (class "Default")
      (node (ref "U9") (pin "VBAT") (pinfunction "VBAT_VBAT") (pintype "passive"))
    )
  )
)
